# keyboard.net
KiCad netlist of a schematic drawn in EAGLE
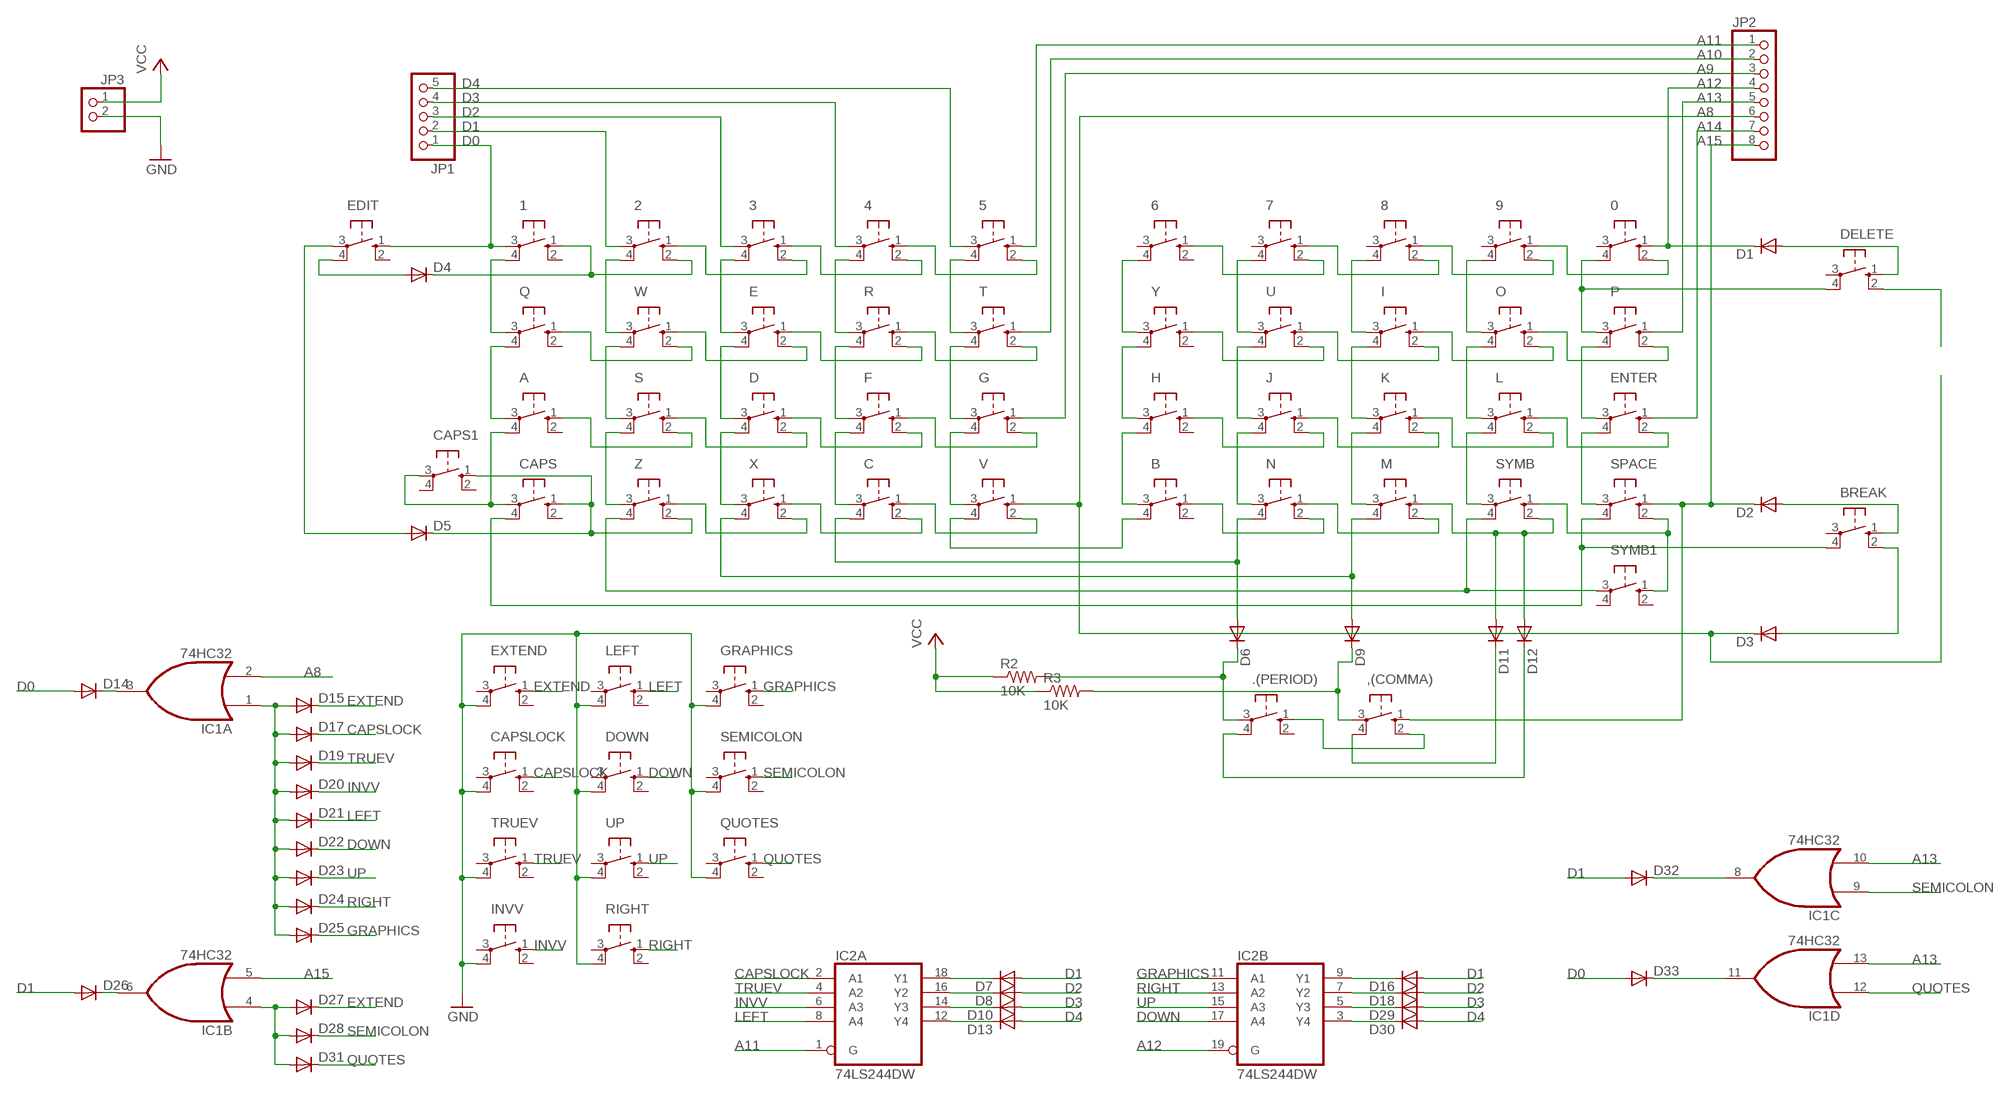
[diagram p0: schematic, sheet 1]

(export (version "E")
  (design (tool "Eeschema 10.0.6"))
  (components
    (comp (ref ",(COMMA)")
      (value "40-XX")
      (footprint "eagle-import:B3F-40XX")
      (fields (field (name "MF") "OMRON COMPONENTS USA") (field (name "MPN") "B3F-4000"))
      (libsource (lib "eagle-import") (part "40-XX"))
    )
    (comp (ref ".(PERIOD)")
      (value "40-XX")
      (footprint "eagle-import:B3F-40XX")
      (fields (field (name "MF") "OMRON COMPONENTS USA") (field (name "MPN") "B3F-4000"))
      (libsource (lib "eagle-import") (part "40-XX"))
    )
    (comp (ref "0")
      (value "40-XX")
      (footprint "eagle-import:B3F-40XX")
      (fields (field (name "MF") "OMRON COMPONENTS USA") (field (name "MPN") "B3F-4000"))
      (libsource (lib "eagle-import") (part "40-XX"))
    )
    (comp (ref "1")
      (value "40-XX")
      (footprint "eagle-import:B3F-40XX")
      (fields (field (name "MF") "OMRON COMPONENTS USA") (field (name "MPN") "B3F-4000"))
      (libsource (lib "eagle-import") (part "40-XX"))
    )
    (comp (ref "2")
      (value "40-XX")
      (footprint "eagle-import:B3F-40XX")
      (fields (field (name "MF") "OMRON COMPONENTS USA") (field (name "MPN") "B3F-4000"))
      (libsource (lib "eagle-import") (part "40-XX"))
    )
    (comp (ref "3")
      (value "40-XX")
      (footprint "eagle-import:B3F-40XX")
      (fields (field (name "MF") "OMRON COMPONENTS USA") (field (name "MPN") "B3F-4000"))
      (libsource (lib "eagle-import") (part "40-XX"))
    )
    (comp (ref "4")
      (value "40-XX")
      (footprint "eagle-import:B3F-40XX")
      (fields (field (name "MF") "OMRON COMPONENTS USA") (field (name "MPN") "B3F-4000"))
      (libsource (lib "eagle-import") (part "40-XX"))
    )
    (comp (ref "5")
      (value "40-XX")
      (footprint "eagle-import:B3F-40XX")
      (fields (field (name "MF") "OMRON COMPONENTS USA") (field (name "MPN") "B3F-4000"))
      (libsource (lib "eagle-import") (part "40-XX"))
    )
    (comp (ref "6")
      (value "40-XX")
      (footprint "eagle-import:B3F-40XX")
      (fields (field (name "MF") "OMRON COMPONENTS USA") (field (name "MPN") "B3F-4000"))
      (libsource (lib "eagle-import") (part "40-XX"))
    )
    (comp (ref "7")
      (value "40-XX")
      (footprint "eagle-import:B3F-40XX")
      (fields (field (name "MF") "OMRON COMPONENTS USA") (field (name "MPN") "B3F-4000"))
      (libsource (lib "eagle-import") (part "40-XX"))
    )
    (comp (ref "8")
      (value "40-XX")
      (footprint "eagle-import:B3F-40XX")
      (fields (field (name "MF") "OMRON COMPONENTS USA") (field (name "MPN") "B3F-4000"))
      (libsource (lib "eagle-import") (part "40-XX"))
    )
    (comp (ref "9")
      (value "40-XX")
      (footprint "eagle-import:B3F-40XX")
      (fields (field (name "MF") "OMRON COMPONENTS USA") (field (name "MPN") "B3F-4000"))
      (libsource (lib "eagle-import") (part "40-XX"))
    )
    (comp (ref "A")
      (value "40-XX")
      (footprint "eagle-import:B3F-40XX")
      (fields (field (name "MF") "OMRON COMPONENTS USA") (field (name "MPN") "B3F-4000"))
      (libsource (lib "eagle-import") (part "40-XX"))
    )
    (comp (ref "B")
      (value "40-XX")
      (footprint "eagle-import:B3F-40XX")
      (fields (field (name "MF") "OMRON COMPONENTS USA") (field (name "MPN") "B3F-4000"))
      (libsource (lib "eagle-import") (part "40-XX"))
    )
    (comp (ref "BREAK")
      (value "40-XX")
      (footprint "eagle-import:B3F-40XX")
      (fields (field (name "MF") "OMRON COMPONENTS USA") (field (name "MPN") "B3F-4000"))
      (libsource (lib "eagle-import") (part "40-XX"))
    )
    (comp (ref "C")
      (value "40-XX")
      (footprint "eagle-import:B3F-40XX")
      (fields (field (name "MF") "OMRON COMPONENTS USA") (field (name "MPN") "B3F-4000"))
      (libsource (lib "eagle-import") (part "40-XX"))
    )
    (comp (ref "CAPS")
      (value "40-XX")
      (footprint "eagle-import:B3F-40XX")
      (fields (field (name "MF") "OMRON COMPONENTS USA") (field (name "MPN") "B3F-4000"))
      (libsource (lib "eagle-import") (part "40-XX"))
    )
    (comp (ref "CAPS1")
      (value "40-XX")
      (footprint "eagle-import:B3F-40XX")
      (fields (field (name "MF") "OMRON COMPONENTS USA") (field (name "MPN") "B3F-4000"))
      (libsource (lib "eagle-import") (part "40-XX"))
    )
    (comp (ref "CAPSLOCK")
      (value "40-XX")
      (footprint "eagle-import:B3F-40XX")
      (fields (field (name "MF") "OMRON COMPONENTS USA") (field (name "MPN") "B3F-4000"))
      (libsource (lib "eagle-import") (part "40-XX"))
    )
    (comp (ref "D")
      (value "40-XX")
      (footprint "eagle-import:B3F-40XX")
      (fields (field (name "MF") "OMRON COMPONENTS USA") (field (name "MPN") "B3F-4000"))
      (libsource (lib "eagle-import") (part "40-XX"))
    )
    (comp (ref "D1")
      (value "DIODE-SMC")
      (footprint "eagle-import:SMC")
      (libsource (lib "eagle-import") (part "DIODE-SMC"))
    )
    (comp (ref "D2")
      (value "DIODE-SMC")
      (footprint "eagle-import:SMC")
      (libsource (lib "eagle-import") (part "DIODE-SMC"))
    )
    (comp (ref "D3")
      (value "DIODE-SMC")
      (footprint "eagle-import:SMC")
      (libsource (lib "eagle-import") (part "DIODE-SMC"))
    )
    (comp (ref "D4")
      (value "DIODE-SMC")
      (footprint "eagle-import:SMC")
      (libsource (lib "eagle-import") (part "DIODE-SMC"))
    )
    (comp (ref "D5")
      (value "DIODE-SMC")
      (footprint "eagle-import:SMC")
      (libsource (lib "eagle-import") (part "DIODE-SMC"))
    )
    (comp (ref "D6")
      (value "DIODE-SMC")
      (footprint "eagle-import:SMC")
      (libsource (lib "eagle-import") (part "DIODE-SMC"))
    )
    (comp (ref "D7")
      (value "DIODE-SMC")
      (footprint "eagle-import:SMC")
      (libsource (lib "eagle-import") (part "DIODE-SMC"))
    )
    (comp (ref "D8")
      (value "DIODE-SMC")
      (footprint "eagle-import:SMC")
      (libsource (lib "eagle-import") (part "DIODE-SMC"))
    )
    (comp (ref "D9")
      (value "DIODE-SMC")
      (footprint "eagle-import:SMC")
      (libsource (lib "eagle-import") (part "DIODE-SMC"))
    )
    (comp (ref "D10")
      (value "DIODE-SMC")
      (footprint "eagle-import:SMC")
      (libsource (lib "eagle-import") (part "DIODE-SMC"))
    )
    (comp (ref "D11")
      (value "DIODE-SMC")
      (footprint "eagle-import:SMC")
      (libsource (lib "eagle-import") (part "DIODE-SMC"))
    )
    (comp (ref "D12")
      (value "DIODE-SMC")
      (footprint "eagle-import:SMC")
      (libsource (lib "eagle-import") (part "DIODE-SMC"))
    )
    (comp (ref "D13")
      (value "DIODE-SMC")
      (footprint "eagle-import:SMC")
      (libsource (lib "eagle-import") (part "DIODE-SMC"))
    )
    (comp (ref "D14")
      (value "DIODE-SMC")
      (footprint "eagle-import:SMC")
      (libsource (lib "eagle-import") (part "DIODE-SMC"))
    )
    (comp (ref "D15")
      (value "DIODE-SMC")
      (footprint "eagle-import:SMC")
      (libsource (lib "eagle-import") (part "DIODE-SMC"))
    )
    (comp (ref "D16")
      (value "DIODE-SMC")
      (footprint "eagle-import:SMC")
      (libsource (lib "eagle-import") (part "DIODE-SMC"))
    )
    (comp (ref "D17")
      (value "DIODE-SMC")
      (footprint "eagle-import:SMC")
      (libsource (lib "eagle-import") (part "DIODE-SMC"))
    )
    (comp (ref "D18")
      (value "DIODE-SMC")
      (footprint "eagle-import:SMC")
      (libsource (lib "eagle-import") (part "DIODE-SMC"))
    )
    (comp (ref "D19")
      (value "DIODE-SMC")
      (footprint "eagle-import:SMC")
      (libsource (lib "eagle-import") (part "DIODE-SMC"))
    )
    (comp (ref "D20")
      (value "DIODE-SMC")
      (footprint "eagle-import:SMC")
      (libsource (lib "eagle-import") (part "DIODE-SMC"))
    )
    (comp (ref "D21")
      (value "DIODE-SMC")
      (footprint "eagle-import:SMC")
      (libsource (lib "eagle-import") (part "DIODE-SMC"))
    )
    (comp (ref "D22")
      (value "DIODE-SMC")
      (footprint "eagle-import:SMC")
      (libsource (lib "eagle-import") (part "DIODE-SMC"))
    )
    (comp (ref "D23")
      (value "DIODE-SMC")
      (footprint "eagle-import:SMC")
      (libsource (lib "eagle-import") (part "DIODE-SMC"))
    )
    (comp (ref "D24")
      (value "DIODE-SMC")
      (footprint "eagle-import:SMC")
      (libsource (lib "eagle-import") (part "DIODE-SMC"))
    )
    (comp (ref "D25")
      (value "DIODE-SMC")
      (footprint "eagle-import:SMC")
      (libsource (lib "eagle-import") (part "DIODE-SMC"))
    )
    (comp (ref "D26")
      (value "DIODE-SMC")
      (footprint "eagle-import:SMC")
      (libsource (lib "eagle-import") (part "DIODE-SMC"))
    )
    (comp (ref "D27")
      (value "DIODE-SMC")
      (footprint "eagle-import:SMC")
      (libsource (lib "eagle-import") (part "DIODE-SMC"))
    )
    (comp (ref "D28")
      (value "DIODE-SMC")
      (footprint "eagle-import:SMC")
      (libsource (lib "eagle-import") (part "DIODE-SMC"))
    )
    (comp (ref "D29")
      (value "DIODE-SMC")
      (footprint "eagle-import:SMC")
      (libsource (lib "eagle-import") (part "DIODE-SMC"))
    )
    (comp (ref "D30")
      (value "DIODE-SMC")
      (footprint "eagle-import:SMC")
      (libsource (lib "eagle-import") (part "DIODE-SMC"))
    )
    (comp (ref "D31")
      (value "DIODE-SMC")
      (footprint "eagle-import:SMC")
      (libsource (lib "eagle-import") (part "DIODE-SMC"))
    )
    (comp (ref "D32")
      (value "DIODE-SMC")
      (footprint "eagle-import:SMC")
      (libsource (lib "eagle-import") (part "DIODE-SMC"))
    )
    (comp (ref "D33")
      (value "DIODE-SMC")
      (footprint "eagle-import:SMC")
      (libsource (lib "eagle-import") (part "DIODE-SMC"))
    )
    (comp (ref "DELETE")
      (value "40-XX")
      (footprint "eagle-import:B3F-40XX")
      (fields (field (name "MF") "OMRON COMPONENTS USA") (field (name "MPN") "B3F-4000"))
      (libsource (lib "eagle-import") (part "40-XX"))
    )
    (comp (ref "DOWN")
      (value "40-XX")
      (footprint "eagle-import:B3F-40XX")
      (fields (field (name "MF") "OMRON COMPONENTS USA") (field (name "MPN") "B3F-4000"))
      (libsource (lib "eagle-import") (part "40-XX"))
    )
    (comp (ref "E")
      (value "40-XX")
      (footprint "eagle-import:B3F-40XX")
      (fields (field (name "MF") "OMRON COMPONENTS USA") (field (name "MPN") "B3F-4000"))
      (libsource (lib "eagle-import") (part "40-XX"))
    )
    (comp (ref "EDIT")
      (value "40-XX")
      (footprint "eagle-import:B3F-40XX")
      (fields (field (name "MF") "OMRON COMPONENTS USA") (field (name "MPN") "B3F-4000"))
      (libsource (lib "eagle-import") (part "40-XX"))
    )
    (comp (ref "ENTER")
      (value "40-XX")
      (footprint "eagle-import:B3F-40XX")
      (fields (field (name "MF") "OMRON COMPONENTS USA") (field (name "MPN") "B3F-4000"))
      (libsource (lib "eagle-import") (part "40-XX"))
    )
    (comp (ref "EXTEND")
      (value "40-XX")
      (footprint "eagle-import:B3F-40XX")
      (fields (field (name "MF") "OMRON COMPONENTS USA") (field (name "MPN") "B3F-4000"))
      (libsource (lib "eagle-import") (part "40-XX"))
    )
    (comp (ref "F")
      (value "40-XX")
      (footprint "eagle-import:B3F-40XX")
      (fields (field (name "MF") "OMRON COMPONENTS USA") (field (name "MPN") "B3F-4000"))
      (libsource (lib "eagle-import") (part "40-XX"))
    )
    (comp (ref "G")
      (value "40-XX")
      (footprint "eagle-import:B3F-40XX")
      (fields (field (name "MF") "OMRON COMPONENTS USA") (field (name "MPN") "B3F-4000"))
      (libsource (lib "eagle-import") (part "40-XX"))
    )
    (comp (ref "GRAPHICS")
      (value "40-XX")
      (footprint "eagle-import:B3F-40XX")
      (fields (field (name "MF") "OMRON COMPONENTS USA") (field (name "MPN") "B3F-4000"))
      (libsource (lib "eagle-import") (part "40-XX"))
    )
    (comp (ref "H")
      (value "40-XX")
      (footprint "eagle-import:B3F-40XX")
      (fields (field (name "MF") "OMRON COMPONENTS USA") (field (name "MPN") "B3F-4000"))
      (libsource (lib "eagle-import") (part "40-XX"))
    )
    (comp (ref "I")
      (value "40-XX")
      (footprint "eagle-import:B3F-40XX")
      (fields (field (name "MF") "OMRON COMPONENTS USA") (field (name "MPN") "B3F-4000"))
      (libsource (lib "eagle-import") (part "40-XX"))
    )
    (comp (ref "IC1")
      (value "74HC32")
      (footprint "eagle-import:SO14")
      (libsource (lib "eagle-import") (part "7432DS"))
    )
    (comp (ref "IC2")
      (value "74LS244DW")
      (footprint "eagle-import:SO20W")
      (libsource (lib "eagle-import") (part "74244DWLS"))
    )
    (comp (ref "INVV")
      (value "40-XX")
      (footprint "eagle-import:B3F-40XX")
      (fields (field (name "MF") "OMRON COMPONENTS USA") (field (name "MPN") "B3F-4000"))
      (libsource (lib "eagle-import") (part "40-XX"))
    )
    (comp (ref "J")
      (value "40-XX")
      (footprint "eagle-import:B3F-40XX")
      (fields (field (name "MF") "OMRON COMPONENTS USA") (field (name "MPN") "B3F-4000"))
      (libsource (lib "eagle-import") (part "40-XX"))
    )
    (comp (ref "JP1")
      (value "PINHD-1X5")
      (footprint "eagle-import:1X05")
      (libsource (lib "eagle-import") (part "PINHD-1X5"))
    )
    (comp (ref "JP2")
      (value "PINHD-1X8")
      (footprint "eagle-import:1X08")
      (libsource (lib "eagle-import") (part "PINHD-1X8"))
    )
    (comp (ref "JP3")
      (value "PINHD-1X2")
      (footprint "eagle-import:1X02")
      (libsource (lib "eagle-import") (part "PINHD-1X2"))
    )
    (comp (ref "K")
      (value "40-XX")
      (footprint "eagle-import:B3F-40XX")
      (fields (field (name "MF") "OMRON COMPONENTS USA") (field (name "MPN") "B3F-4000"))
      (libsource (lib "eagle-import") (part "40-XX"))
    )
    (comp (ref "L")
      (value "40-XX")
      (footprint "eagle-import:B3F-40XX")
      (fields (field (name "MF") "OMRON COMPONENTS USA") (field (name "MPN") "B3F-4000"))
      (libsource (lib "eagle-import") (part "40-XX"))
    )
    (comp (ref "LEFT")
      (value "40-XX")
      (footprint "eagle-import:B3F-40XX")
      (fields (field (name "MF") "OMRON COMPONENTS USA") (field (name "MPN") "B3F-4000"))
      (libsource (lib "eagle-import") (part "40-XX"))
    )
    (comp (ref "M")
      (value "40-XX")
      (footprint "eagle-import:B3F-40XX")
      (fields (field (name "MF") "OMRON COMPONENTS USA") (field (name "MPN") "B3F-4000"))
      (libsource (lib "eagle-import") (part "40-XX"))
    )
    (comp (ref "N")
      (value "40-XX")
      (footprint "eagle-import:B3F-40XX")
      (fields (field (name "MF") "OMRON COMPONENTS USA") (field (name "MPN") "B3F-4000"))
      (libsource (lib "eagle-import") (part "40-XX"))
    )
    (comp (ref "O")
      (value "40-XX")
      (footprint "eagle-import:B3F-40XX")
      (fields (field (name "MF") "OMRON COMPONENTS USA") (field (name "MPN") "B3F-4000"))
      (libsource (lib "eagle-import") (part "40-XX"))
    )
    (comp (ref "P")
      (value "40-XX")
      (footprint "eagle-import:B3F-40XX")
      (fields (field (name "MF") "OMRON COMPONENTS USA") (field (name "MPN") "B3F-4000"))
      (libsource (lib "eagle-import") (part "40-XX"))
    )
    (comp (ref "Q")
      (value "40-XX")
      (footprint "eagle-import:B3F-40XX")
      (fields (field (name "MF") "OMRON COMPONENTS USA") (field (name "MPN") "B3F-4000"))
      (libsource (lib "eagle-import") (part "40-XX"))
    )
    (comp (ref "QUOTES")
      (value "40-XX")
      (footprint "eagle-import:B3F-40XX")
      (fields (field (name "MF") "OMRON COMPONENTS USA") (field (name "MPN") "B3F-4000"))
      (libsource (lib "eagle-import") (part "40-XX"))
    )
    (comp (ref "R")
      (value "40-XX")
      (footprint "eagle-import:B3F-40XX")
      (fields (field (name "MF") "OMRON COMPONENTS USA") (field (name "MPN") "B3F-4000"))
      (libsource (lib "eagle-import") (part "40-XX"))
    )
    (comp (ref "R2")
      (value "10K")
      (footprint "eagle-import:M0805")
      (libsource (lib "eagle-import") (part "R-US_M0805"))
    )
    (comp (ref "R3")
      (value "10K")
      (footprint "eagle-import:M0805")
      (libsource (lib "eagle-import") (part "R-US_M0805"))
    )
    (comp (ref "RIGHT")
      (value "40-XX")
      (footprint "eagle-import:B3F-40XX")
      (fields (field (name "MF") "OMRON COMPONENTS USA") (field (name "MPN") "B3F-4000"))
      (libsource (lib "eagle-import") (part "40-XX"))
    )
    (comp (ref "S")
      (value "40-XX")
      (footprint "eagle-import:B3F-40XX")
      (fields (field (name "MF") "OMRON COMPONENTS USA") (field (name "MPN") "B3F-4000"))
      (libsource (lib "eagle-import") (part "40-XX"))
    )
    (comp (ref "SEMICOLON")
      (value "40-XX")
      (footprint "eagle-import:B3F-40XX")
      (fields (field (name "MF") "OMRON COMPONENTS USA") (field (name "MPN") "B3F-4000"))
      (libsource (lib "eagle-import") (part "40-XX"))
    )
    (comp (ref "SPACE")
      (value "40-XX")
      (footprint "eagle-import:B3F-40XX")
      (fields (field (name "MF") "OMRON COMPONENTS USA") (field (name "MPN") "B3F-4000"))
      (libsource (lib "eagle-import") (part "40-XX"))
    )
    (comp (ref "SYMB")
      (value "40-XX")
      (footprint "eagle-import:B3F-40XX")
      (fields (field (name "MF") "OMRON COMPONENTS USA") (field (name "MPN") "B3F-4000"))
      (libsource (lib "eagle-import") (part "40-XX"))
    )
    (comp (ref "SYMB1")
      (value "40-XX")
      (footprint "eagle-import:B3F-40XX")
      (fields (field (name "MF") "OMRON COMPONENTS USA") (field (name "MPN") "B3F-4000"))
      (libsource (lib "eagle-import") (part "40-XX"))
    )
    (comp (ref "T")
      (value "40-XX")
      (footprint "eagle-import:B3F-40XX")
      (fields (field (name "MF") "OMRON COMPONENTS USA") (field (name "MPN") "B3F-4000"))
      (libsource (lib "eagle-import") (part "40-XX"))
    )
    (comp (ref "TRUEV")
      (value "40-XX")
      (footprint "eagle-import:B3F-40XX")
      (fields (field (name "MF") "OMRON COMPONENTS USA") (field (name "MPN") "B3F-4000"))
      (libsource (lib "eagle-import") (part "40-XX"))
    )
    (comp (ref "U")
      (value "40-XX")
      (footprint "eagle-import:B3F-40XX")
      (fields (field (name "MF") "OMRON COMPONENTS USA") (field (name "MPN") "B3F-4000"))
      (libsource (lib "eagle-import") (part "40-XX"))
    )
    (comp (ref "UP")
      (value "40-XX")
      (footprint "eagle-import:B3F-40XX")
      (fields (field (name "MF") "OMRON COMPONENTS USA") (field (name "MPN") "B3F-4000"))
      (libsource (lib "eagle-import") (part "40-XX"))
    )
    (comp (ref "V")
      (value "40-XX")
      (footprint "eagle-import:B3F-40XX")
      (fields (field (name "MF") "OMRON COMPONENTS USA") (field (name "MPN") "B3F-4000"))
      (libsource (lib "eagle-import") (part "40-XX"))
    )
    (comp (ref "W")
      (value "40-XX")
      (footprint "eagle-import:B3F-40XX")
      (fields (field (name "MF") "OMRON COMPONENTS USA") (field (name "MPN") "B3F-4000"))
      (libsource (lib "eagle-import") (part "40-XX"))
    )
    (comp (ref "X")
      (value "40-XX")
      (footprint "eagle-import:B3F-40XX")
      (fields (field (name "MF") "OMRON COMPONENTS USA") (field (name "MPN") "B3F-4000"))
      (libsource (lib "eagle-import") (part "40-XX"))
    )
    (comp (ref "Y")
      (value "40-XX")
      (footprint "eagle-import:B3F-40XX")
      (fields (field (name "MF") "OMRON COMPONENTS USA") (field (name "MPN") "B3F-4000"))
      (libsource (lib "eagle-import") (part "40-XX"))
    )
    (comp (ref "Z")
      (value "40-XX")
      (footprint "eagle-import:B3F-40XX")
      (fields (field (name "MF") "OMRON COMPONENTS USA") (field (name "MPN") "B3F-4000"))
      (libsource (lib "eagle-import") (part "40-XX"))
    )
  )
  (nets
    (net (code "1") (name "/A8") (class "Default")
      (node (ref "D3") (pin "C") (pinfunction "C_C") (pintype "passive"))
      (node (ref "IC1") (pin "2") (pinfunction "I1_2") (pintype "input"))
      (node (ref "JP2") (pin "6") (pinfunction "6_6") (pintype "passive"))
      (node (ref "V") (pin "1") (pinfunction "S_1") (pintype "passive"))
    )
    (net (code "2") (name "/A9") (class "Default")
      (node (ref "G") (pin "1") (pinfunction "S_1") (pintype "passive"))
      (node (ref "JP2") (pin "3") (pinfunction "3_3") (pintype "passive"))
    )
    (net (code "3") (name "/A10") (class "Default")
      (node (ref "JP2") (pin "2") (pinfunction "2_2") (pintype "passive"))
      (node (ref "T") (pin "1") (pinfunction "S_1") (pintype "passive"))
    )
    (net (code "4") (name "/A11") (class "Default")
      (node (ref "5") (pin "1") (pinfunction "S_1") (pintype "passive"))
      (node (ref "IC2") (pin "1") (pinfunction "G_1") (pintype "input"))
      (node (ref "JP2") (pin "1") (pinfunction "1_1") (pintype "passive"))
    )
    (net (code "5") (name "/A12") (class "Default")
      (node (ref "0") (pin "1") (pinfunction "S_1") (pintype "passive"))
      (node (ref "D1") (pin "C") (pinfunction "C_C") (pintype "passive"))
      (node (ref "IC2") (pin "19") (pinfunction "G_19") (pintype "input"))
      (node (ref "JP2") (pin "4") (pinfunction "4_4") (pintype "passive"))
    )
    (net (code "6") (name "/A13") (class "Default")
      (node (ref "IC1") (pin "10") (pinfunction "I1_10") (pintype "input"))
      (node (ref "IC1") (pin "13") (pinfunction "I1_13") (pintype "input"))
      (node (ref "JP2") (pin "5") (pinfunction "5_5") (pintype "passive"))
      (node (ref "P") (pin "1") (pinfunction "S_1") (pintype "passive"))
    )
    (net (code "7") (name "/A14") (class "Default")
      (node (ref "ENTER") (pin "1") (pinfunction "S_1") (pintype "passive"))
      (node (ref "JP2") (pin "7") (pinfunction "7_7") (pintype "passive"))
    )
    (net (code "8") (name "/A15") (class "Default")
      (node (ref ",(COMMA)") (pin "1") (pinfunction "S_1") (pintype "passive"))
      (node (ref "D2") (pin "C") (pinfunction "C_C") (pintype "passive"))
      (node (ref "IC1") (pin "5") (pinfunction "I1_5") (pintype "input"))
      (node (ref "JP2") (pin "8") (pinfunction "8_8") (pintype "passive"))
      (node (ref "SPACE") (pin "1") (pinfunction "S_1") (pintype "passive"))
    )
    (net (code "9") (name "/CAPSLOCK") (class "Default")
      (node (ref "CAPSLOCK") (pin "1") (pinfunction "S_1") (pintype "passive"))
      (node (ref "D17") (pin "C") (pinfunction "C_C") (pintype "passive"))
      (node (ref "IC2") (pin "2") (pinfunction "A1_2") (pintype "input"))
    )
    (net (code "10") (name "/D0") (class "Default")
      (node (ref "1") (pin "3") (pinfunction "P_3") (pintype "passive"))
      (node (ref "D14") (pin "A") (pinfunction "A_A") (pintype "passive"))
      (node (ref "D33") (pin "A") (pinfunction "A_A") (pintype "passive"))
      (node (ref "EDIT") (pin "1") (pinfunction "S_1") (pintype "passive"))
      (node (ref "JP1") (pin "1") (pinfunction "1_1") (pintype "passive"))
    )
    (net (code "11") (name "/D1") (class "Default")
      (node (ref "2") (pin "3") (pinfunction "P_3") (pintype "passive"))
      (node (ref "D16") (pin "A") (pinfunction "A_A") (pintype "passive"))
      (node (ref "D26") (pin "A") (pinfunction "A_A") (pintype "passive"))
      (node (ref "D32") (pin "A") (pinfunction "A_A") (pintype "passive"))
      (node (ref "D7") (pin "A") (pinfunction "A_A") (pintype "passive"))
      (node (ref "JP1") (pin "2") (pinfunction "2_2") (pintype "passive"))
    )
    (net (code "12") (name "/D2") (class "Default")
      (node (ref "3") (pin "3") (pinfunction "P_3") (pintype "passive"))
      (node (ref "D18") (pin "A") (pinfunction "A_A") (pintype "passive"))
      (node (ref "D8") (pin "A") (pinfunction "A_A") (pintype "passive"))
      (node (ref "JP1") (pin "3") (pinfunction "3_3") (pintype "passive"))
    )
    (net (code "13") (name "/D3") (class "Default")
      (node (ref "4") (pin "3") (pinfunction "P_3") (pintype "passive"))
      (node (ref "D10") (pin "A") (pinfunction "A_A") (pintype "passive"))
      (node (ref "D29") (pin "A") (pinfunction "A_A") (pintype "passive"))
      (node (ref "JP1") (pin "4") (pinfunction "4_4") (pintype "passive"))
    )
    (net (code "14") (name "/D4") (class "Default")
      (node (ref "5") (pin "3") (pinfunction "P_3") (pintype "passive"))
      (node (ref "D13") (pin "A") (pinfunction "A_A") (pintype "passive"))
      (node (ref "D30") (pin "A") (pinfunction "A_A") (pintype "passive"))
      (node (ref "JP1") (pin "5") (pinfunction "5_5") (pintype "passive"))
    )
    (net (code "15") (name "/DOWN") (class "Default")
      (node (ref "D22") (pin "C") (pinfunction "C_C") (pintype "passive"))
      (node (ref "DOWN") (pin "1") (pinfunction "S_1") (pintype "passive"))
      (node (ref "IC2") (pin "17") (pinfunction "A4_17") (pintype "input"))
    )
    (net (code "16") (name "/EXTEND") (class "Default")
      (node (ref "D15") (pin "C") (pinfunction "C_C") (pintype "passive"))
      (node (ref "D27") (pin "C") (pinfunction "C_C") (pintype "passive"))
      (node (ref "EXTEND") (pin "1") (pinfunction "S_1") (pintype "passive"))
    )
    (net (code "17") (name "/GRAPHICS") (class "Default")
      (node (ref "D25") (pin "C") (pinfunction "C_C") (pintype "passive"))
      (node (ref "GRAPHICS") (pin "1") (pinfunction "S_1") (pintype "passive"))
      (node (ref "IC2") (pin "11") (pinfunction "A1_11") (pintype "input"))
    )
    (net (code "18") (name "/INVV") (class "Default")
      (node (ref "D20") (pin "C") (pinfunction "C_C") (pintype "passive"))
      (node (ref "IC2") (pin "6") (pinfunction "A3_6") (pintype "input"))
      (node (ref "INVV") (pin "1") (pinfunction "S_1") (pintype "passive"))
    )
    (net (code "19") (name "/LEFT") (class "Default")
      (node (ref "D21") (pin "C") (pinfunction "C_C") (pintype "passive"))
      (node (ref "IC2") (pin "8") (pinfunction "A4_8") (pintype "input"))
      (node (ref "LEFT") (pin "1") (pinfunction "S_1") (pintype "passive"))
    )
    (net (code "20") (name "/QUOTES") (class "Default")
      (node (ref "D31") (pin "C") (pinfunction "C_C") (pintype "passive"))
      (node (ref "IC1") (pin "12") (pinfunction "I0_12") (pintype "input"))
      (node (ref "QUOTES") (pin "1") (pinfunction "S_1") (pintype "passive"))
    )
    (net (code "21") (name "/RIGHT") (class "Default")
      (node (ref "D24") (pin "C") (pinfunction "C_C") (pintype "passive"))
      (node (ref "IC2") (pin "13") (pinfunction "A2_13") (pintype "input"))
      (node (ref "RIGHT") (pin "1") (pinfunction "S_1") (pintype "passive"))
    )
    (net (code "22") (name "/SEMICOLON") (class "Default")
      (node (ref "D28") (pin "C") (pinfunction "C_C") (pintype "passive"))
      (node (ref "IC1") (pin "9") (pinfunction "I0_9") (pintype "input"))
      (node (ref "SEMICOLON") (pin "1") (pinfunction "S_1") (pintype "passive"))
    )
    (net (code "23") (name "/TRUEV") (class "Default")
      (node (ref "D19") (pin "C") (pinfunction "C_C") (pintype "passive"))
      (node (ref "IC2") (pin "4") (pinfunction "A2_4") (pintype "input"))
      (node (ref "TRUEV") (pin "1") (pinfunction "S_1") (pintype "passive"))
    )
    (net (code "24") (name "/UP") (class "Default")
      (node (ref "D23") (pin "C") (pinfunction "C_C") (pintype "passive"))
      (node (ref "IC2") (pin "15") (pinfunction "A3_15") (pintype "input"))
      (node (ref "UP") (pin "1") (pinfunction "S_1") (pintype "passive"))
    )
    (net (code "25") (name "GND") (class "Default")
      (node (ref "CAPSLOCK") (pin "4") (pinfunction "P1_4") (pintype "passive"))
      (node (ref "DOWN") (pin "4") (pinfunction "P1_4") (pintype "passive"))
      (node (ref "EXTEND") (pin "4") (pinfunction "P1_4") (pintype "passive"))
      (node (ref "GRAPHICS") (pin "4") (pinfunction "P1_4") (pintype "passive"))
      (node (ref "INVV") (pin "4") (pinfunction "P1_4") (pintype "passive"))
      (node (ref "JP3") (pin "2") (pinfunction "2_2") (pintype "passive"))
      (node (ref "LEFT") (pin "4") (pinfunction "P1_4") (pintype "passive"))
      (node (ref "QUOTES") (pin "4") (pinfunction "P1_4") (pintype "passive"))
      (node (ref "RIGHT") (pin "4") (pinfunction "P1_4") (pintype "passive"))
      (node (ref "SEMICOLON") (pin "4") (pinfunction "P1_4") (pintype "passive"))
      (node (ref "TRUEV") (pin "4") (pinfunction "P1_4") (pintype "passive"))
      (node (ref "UP") (pin "4") (pinfunction "P1_4") (pintype "passive"))
    )
    (net (code "26") (name "Net-(,(COMMA)-P)") (class "Default")
      (node (ref ",(COMMA)") (pin "3") (pinfunction "P_3") (pintype "passive"))
      (node (ref "D9") (pin "C") (pinfunction "C_C") (pintype "passive"))
      (node (ref "R3") (pin "2") (pinfunction "2_2") (pintype "passive"))
    )
    (net (code "27") (name "Net-(,(COMMA)-P1)") (class "Default")
      (node (ref ",(COMMA)") (pin "4") (pinfunction "P1_4") (pintype "passive"))
      (node (ref "D11") (pin "C") (pinfunction "C_C") (pintype "passive"))
    )
    (net (code "28") (name "Net-(,(COMMA)-S1)") (class "Default")
      (node (ref ",(COMMA)") (pin "2") (pinfunction "S1_2") (pintype "passive"))
      (node (ref ".(PERIOD)") (pin "1") (pinfunction "S_1") (pintype "passive"))
    )
    (net (code "29") (name "Net-(.(PERIOD)-P)") (class "Default")
      (node (ref ".(PERIOD)") (pin "3") (pinfunction "P_3") (pintype "passive"))
      (node (ref "D6") (pin "C") (pinfunction "C_C") (pintype "passive"))
      (node (ref "R2") (pin "2") (pinfunction "2_2") (pintype "passive"))
    )
    (net (code "30") (name "Net-(.(PERIOD)-P1)") (class "Default")
      (node (ref ".(PERIOD)") (pin "4") (pinfunction "P1_4") (pintype "passive"))
      (node (ref "D12") (pin "C") (pinfunction "C_C") (pintype "passive"))
    )
    (net (code "31") (name "Net-(0-P1)") (class "Default")
      (node (ref "0") (pin "4") (pinfunction "P1_4") (pintype "passive"))
      (node (ref "DELETE") (pin "4") (pinfunction "P1_4") (pintype "passive"))
      (node (ref "P") (pin "3") (pinfunction "P_3") (pintype "passive"))
    )
    (net (code "32") (name "Net-(0-S1)") (class "Default")
      (node (ref "0") (pin "2") (pinfunction "S1_2") (pintype "passive"))
      (node (ref "9") (pin "1") (pinfunction "S_1") (pintype "passive"))
    )
    (net (code "33") (name "Net-(1-P1)") (class "Default")
      (node (ref "1") (pin "4") (pinfunction "P1_4") (pintype "passive"))
      (node (ref "Q") (pin "3") (pinfunction "P_3") (pintype "passive"))
    )
    (net (code "34") (name "Net-(1-S)") (class "Default")
      (node (ref "1") (pin "1") (pinfunction "S_1") (pintype "passive"))
      (node (ref "2") (pin "2") (pinfunction "S1_2") (pintype "passive"))
      (node (ref "D4") (pin "C") (pinfunction "C_C") (pintype "passive"))
    )
    (net (code "35") (name "Net-(2-P1)") (class "Default")
      (node (ref "2") (pin "4") (pinfunction "P1_4") (pintype "passive"))
      (node (ref "W") (pin "3") (pinfunction "P_3") (pintype "passive"))
    )
    (net (code "36") (name "Net-(2-S)") (class "Default")
      (node (ref "2") (pin "1") (pinfunction "S_1") (pintype "passive"))
      (node (ref "3") (pin "2") (pinfunction "S1_2") (pintype "passive"))
    )
    (net (code "37") (name "Net-(3-P1)") (class "Default")
      (node (ref "3") (pin "4") (pinfunction "P1_4") (pintype "passive"))
      (node (ref "E") (pin "3") (pinfunction "P_3") (pintype "passive"))
    )
    (net (code "38") (name "Net-(3-S)") (class "Default")
      (node (ref "3") (pin "1") (pinfunction "S_1") (pintype "passive"))
      (node (ref "4") (pin "2") (pinfunction "S1_2") (pintype "passive"))
    )
    (net (code "39") (name "Net-(4-P1)") (class "Default")
      (node (ref "4") (pin "4") (pinfunction "P1_4") (pintype "passive"))
      (node (ref "R") (pin "3") (pinfunction "P_3") (pintype "passive"))
    )
    (net (code "40") (name "Net-(4-S)") (class "Default")
      (node (ref "4") (pin "1") (pinfunction "S_1") (pintype "passive"))
      (node (ref "5") (pin "2") (pinfunction "S1_2") (pintype "passive"))
    )
    (net (code "41") (name "Net-(5-P1)") (class "Default")
      (node (ref "5") (pin "4") (pinfunction "P1_4") (pintype "passive"))
      (node (ref "T") (pin "3") (pinfunction "P_3") (pintype "passive"))
    )
    (net (code "42") (name "Net-(6-P1)") (class "Default")
      (node (ref "6") (pin "4") (pinfunction "P1_4") (pintype "passive"))
      (node (ref "Y") (pin "3") (pinfunction "P_3") (pintype "passive"))
    )
    (net (code "43") (name "Net-(6-S)") (class "Default")
      (node (ref "6") (pin "1") (pinfunction "S_1") (pintype "passive"))
      (node (ref "7") (pin "2") (pinfunction "S1_2") (pintype "passive"))
    )
    (net (code "44") (name "Net-(7-P1)") (class "Default")
      (node (ref "7") (pin "4") (pinfunction "P1_4") (pintype "passive"))
      (node (ref "U") (pin "3") (pinfunction "P_3") (pintype "passive"))
    )
    (net (code "45") (name "Net-(7-S)") (class "Default")
      (node (ref "7") (pin "1") (pinfunction "S_1") (pintype "passive"))
      (node (ref "8") (pin "2") (pinfunction "S1_2") (pintype "passive"))
    )
    (net (code "46") (name "Net-(8-P1)") (class "Default")
      (node (ref "8") (pin "4") (pinfunction "P1_4") (pintype "passive"))
      (node (ref "I") (pin "3") (pinfunction "P_3") (pintype "passive"))
    )
    (net (code "47") (name "Net-(8-S)") (class "Default")
      (node (ref "8") (pin "1") (pinfunction "S_1") (pintype "passive"))
      (node (ref "9") (pin "2") (pinfunction "S1_2") (pintype "passive"))
    )
    (net (code "48") (name "Net-(9-P1)") (class "Default")
      (node (ref "9") (pin "4") (pinfunction "P1_4") (pintype "passive"))
      (node (ref "O") (pin "3") (pinfunction "P_3") (pintype "passive"))
    )
    (net (code "49") (name "Net-(A-P)") (class "Default")
      (node (ref "A") (pin "3") (pinfunction "P_3") (pintype "passive"))
      (node (ref "Q") (pin "4") (pinfunction "P1_4") (pintype "passive"))
    )
    (net (code "50") (name "Net-(A-P1)") (class "Default")
      (node (ref "A") (pin "4") (pinfunction "P1_4") (pintype "passive"))
      (node (ref "CAPS") (pin "3") (pinfunction "P_3") (pintype "passive"))
      (node (ref "CAPS1") (pin "3") (pinfunction "P_3") (pintype "passive"))
    )
    (net (code "51") (name "Net-(A-S)") (class "Default")
      (node (ref "A") (pin "1") (pinfunction "S_1") (pintype "passive"))
      (node (ref "S") (pin "2") (pinfunction "S1_2") (pintype "passive"))
    )
    (net (code "52") (name "Net-(B-P)") (class "Default")
      (node (ref "B") (pin "3") (pinfunction "P_3") (pintype "passive"))
      (node (ref "H") (pin "4") (pinfunction "P1_4") (pintype "passive"))
    )
    (net (code "53") (name "Net-(B-P1)") (class "Default")
      (node (ref "B") (pin "4") (pinfunction "P1_4") (pintype "passive"))
      (node (ref "V") (pin "4") (pinfunction "P1_4") (pintype "passive"))
    )
    (net (code "54") (name "Net-(B-S)") (class "Default")
      (node (ref "B") (pin "1") (pinfunction "S_1") (pintype "passive"))
      (node (ref "N") (pin "2") (pinfunction "S1_2") (pintype "passive"))
    )
    (net (code "55") (name "Net-(BREAK-P1)") (class "Default")
      (node (ref "BREAK") (pin "4") (pinfunction "P1_4") (pintype "passive"))
      (node (ref "CAPS") (pin "4") (pinfunction "P1_4") (pintype "passive"))
      (node (ref "SPACE") (pin "4") (pinfunction "P1_4") (pintype "passive"))
    )
    (net (code "56") (name "Net-(BREAK-S)") (class "Default")
      (node (ref "BREAK") (pin "1") (pinfunction "S_1") (pintype "passive"))
      (node (ref "D2") (pin "A") (pinfunction "A_A") (pintype "passive"))
    )
    (net (code "57") (name "Net-(BREAK-S1)") (class "Default")
      (node (ref "BREAK") (pin "2") (pinfunction "S1_2") (pintype "passive"))
      (node (ref "D3") (pin "A") (pinfunction "A_A") (pintype "passive"))
    )
    (net (code "58") (name "Net-(C-P)") (class "Default")
      (node (ref "C") (pin "3") (pinfunction "P_3") (pintype "passive"))
      (node (ref "F") (pin "4") (pinfunction "P1_4") (pintype "passive"))
    )
    (net (code "59") (name "Net-(C-P1)") (class "Default")
      (node (ref "C") (pin "4") (pinfunction "P1_4") (pintype "passive"))
      (node (ref "D6") (pin "A") (pinfunction "A_A") (pintype "passive"))
      (node (ref "N") (pin "4") (pinfunction "P1_4") (pintype "passive"))
    )
    (net (code "60") (name "Net-(C-S)") (class "Default")
      (node (ref "C") (pin "1") (pinfunction "S_1") (pintype "passive"))
      (node (ref "V") (pin "2") (pinfunction "S1_2") (pintype "passive"))
    )
    (net (code "61") (name "Net-(C-S1)") (class "Default")
      (node (ref "C") (pin "2") (pinfunction "S1_2") (pintype "passive"))
      (node (ref "X") (pin "1") (pinfunction "S_1") (pintype "passive"))
    )
    (net (code "62") (name "Net-(CAPS-S)") (class "Default")
      (node (ref "CAPS") (pin "1") (pinfunction "S_1") (pintype "passive"))
      (node (ref "CAPS1") (pin "1") (pinfunction "S_1") (pintype "passive"))
      (node (ref "D5") (pin "C") (pinfunction "C_C") (pintype "passive"))
      (node (ref "Z") (pin "2") (pinfunction "S1_2") (pintype "passive"))
    )
    (net (code "63") (name "Net-(D-P)") (class "Default")
      (node (ref "D") (pin "3") (pinfunction "P_3") (pintype "passive"))
      (node (ref "E") (pin "4") (pinfunction "P1_4") (pintype "passive"))
    )
    (net (code "64") (name "Net-(D-P1)") (class "Default")
      (node (ref "D") (pin "4") (pinfunction "P1_4") (pintype "passive"))
      (node (ref "X") (pin "3") (pinfunction "P_3") (pintype "passive"))
    )
    (net (code "65") (name "Net-(D-S)") (class "Default")
      (node (ref "D") (pin "1") (pinfunction "S_1") (pintype "passive"))
      (node (ref "F") (pin "2") (pinfunction "S1_2") (pintype "passive"))
    )
    (net (code "66") (name "Net-(D-S1)") (class "Default")
      (node (ref "D") (pin "2") (pinfunction "S1_2") (pintype "passive"))
      (node (ref "S") (pin "1") (pinfunction "S_1") (pintype "passive"))
    )
    (net (code "67") (name "Net-(DELETE-S)") (class "Default")
      (node (ref "D1") (pin "A") (pinfunction "A_A") (pintype "passive"))
      (node (ref "DELETE") (pin "1") (pinfunction "S_1") (pintype "passive"))
    )
    (net (code "68") (name "Net-(E-S)") (class "Default")
      (node (ref "E") (pin "1") (pinfunction "S_1") (pintype "passive"))
      (node (ref "R") (pin "2") (pinfunction "S1_2") (pintype "passive"))
    )
    (net (code "69") (name "Net-(E-S1)") (class "Default")
      (node (ref "E") (pin "2") (pinfunction "S1_2") (pintype "passive"))
      (node (ref "W") (pin "1") (pinfunction "S_1") (pintype "passive"))
    )
    (net (code "70") (name "Net-(EDIT-P)") (class "Default")
      (node (ref "D5") (pin "A") (pinfunction "A_A") (pintype "passive"))
      (node (ref "EDIT") (pin "3") (pinfunction "P_3") (pintype "passive"))
    )
    (net (code "71") (name "Net-(EDIT-P1)") (class "Default")
      (node (ref "D4") (pin "A") (pinfunction "A_A") (pintype "passive"))
      (node (ref "EDIT") (pin "4") (pinfunction "P1_4") (pintype "passive"))
    )
    (net (code "72") (name "Net-(ENTER-P)") (class "Default")
      (node (ref "ENTER") (pin "3") (pinfunction "P_3") (pintype "passive"))
      (node (ref "P") (pin "4") (pinfunction "P1_4") (pintype "passive"))
    )
    (net (code "73") (name "Net-(ENTER-P1)") (class "Default")
      (node (ref "ENTER") (pin "4") (pinfunction "P1_4") (pintype "passive"))
      (node (ref "SPACE") (pin "3") (pinfunction "P_3") (pintype "passive"))
    )
    (net (code "74") (name "Net-(ENTER-S1)") (class "Default")
      (node (ref "ENTER") (pin "2") (pinfunction "S1_2") (pintype "passive"))
      (node (ref "L") (pin "1") (pinfunction "S_1") (pintype "passive"))
    )
    (net (code "75") (name "Net-(F-P)") (class "Default")
      (node (ref "F") (pin "3") (pinfunction "P_3") (pintype "passive"))
      (node (ref "R") (pin "4") (pinfunction "P1_4") (pintype "passive"))
    )
    (net (code "76") (name "Net-(F-S)") (class "Default")
      (node (ref "F") (pin "1") (pinfunction "S_1") (pintype "passive"))
      (node (ref "G") (pin "2") (pinfunction "S1_2") (pintype "passive"))
    )
    (net (code "77") (name "Net-(G-P)") (class "Default")
      (node (ref "G") (pin "3") (pinfunction "P_3") (pintype "passive"))
      (node (ref "T") (pin "4") (pinfunction "P1_4") (pintype "passive"))
    )
    (net (code "78") (name "Net-(G-P1)") (class "Default")
      (node (ref "G") (pin "4") (pinfunction "P1_4") (pintype "passive"))
      (node (ref "V") (pin "3") (pinfunction "P_3") (pintype "passive"))
    )
    (net (code "79") (name "Net-(H-P)") (class "Default")
      (node (ref "H") (pin "3") (pinfunction "P_3") (pintype "passive"))
      (node (ref "Y") (pin "4") (pinfunction "P1_4") (pintype "passive"))
    )
    (net (code "80") (name "Net-(H-S)") (class "Default")
      (node (ref "H") (pin "1") (pinfunction "S_1") (pintype "passive"))
      (node (ref "J") (pin "2") (pinfunction "S1_2") (pintype "passive"))
    )
    (net (code "81") (name "Net-(I-P1)") (class "Default")
      (node (ref "I") (pin "4") (pinfunction "P1_4") (pintype "passive"))
      (node (ref "K") (pin "3") (pinfunction "P_3") (pintype "passive"))
    )
    (net (code "82") (name "Net-(I-S)") (class "Default")
      (node (ref "I") (pin "1") (pinfunction "S_1") (pintype "passive"))
      (node (ref "O") (pin "2") (pinfunction "S1_2") (pintype "passive"))
    )
    (net (code "83") (name "Net-(I-S1)") (class "Default")
      (node (ref "I") (pin "2") (pinfunction "S1_2") (pintype "passive"))
      (node (ref "U") (pin "1") (pinfunction "S_1") (pintype "passive"))
    )
    (net (code "84") (name "Net-(IC1A-I0)") (class "Default")
      (node (ref "D15") (pin "A") (pinfunction "A_A") (pintype "passive"))
      (node (ref "D17") (pin "A") (pinfunction "A_A") (pintype "passive"))
      (node (ref "D19") (pin "A") (pinfunction "A_A") (pintype "passive"))
      (node (ref "D20") (pin "A") (pinfunction "A_A") (pintype "passive"))
      (node (ref "D21") (pin "A") (pinfunction "A_A") (pintype "passive"))
      (node (ref "D22") (pin "A") (pinfunction "A_A") (pintype "passive"))
      (node (ref "D23") (pin "A") (pinfunction "A_A") (pintype "passive"))
      (node (ref "D24") (pin "A") (pinfunction "A_A") (pintype "passive"))
      (node (ref "D25") (pin "A") (pinfunction "A_A") (pintype "passive"))
      (node (ref "IC1") (pin "1") (pinfunction "I0_1") (pintype "input"))
    )
    (net (code "85") (name "Net-(IC1A-O)") (class "Default")
      (node (ref "D14") (pin "C") (pinfunction "C_C") (pintype "passive"))
      (node (ref "IC1") (pin "3") (pinfunction "O_3") (pintype "output"))
    )
    (net (code "86") (name "Net-(IC1B-I0)") (class "Default")
      (node (ref "D27") (pin "A") (pinfunction "A_A") (pintype "passive"))
      (node (ref "D28") (pin "A") (pinfunction "A_A") (pintype "passive"))
      (node (ref "D31") (pin "A") (pinfunction "A_A") (pintype "passive"))
      (node (ref "IC1") (pin "4") (pinfunction "I0_4") (pintype "input"))
    )
    (net (code "87") (name "Net-(IC1B-O)") (class "Default")
      (node (ref "D26") (pin "C") (pinfunction "C_C") (pintype "passive"))
      (node (ref "IC1") (pin "6") (pinfunction "O_6") (pintype "output"))
    )
    (net (code "88") (name "Net-(IC1C-O)") (class "Default")
      (node (ref "D32") (pin "C") (pinfunction "C_C") (pintype "passive"))
      (node (ref "IC1") (pin "8") (pinfunction "O_8") (pintype "output"))
    )
    (net (code "89") (name "Net-(IC1D-O)") (class "Default")
      (node (ref "D33") (pin "C") (pinfunction "C_C") (pintype "passive"))
      (node (ref "IC1") (pin "11") (pinfunction "O_11") (pintype "output"))
    )
    (net (code "90") (name "Net-(IC2A-Y1)") (class "Default")
      (node (ref "D7") (pin "C") (pinfunction "C_C") (pintype "passive"))
      (node (ref "IC2") (pin "18") (pinfunction "Y1_18") (pintype "tri_state"))
    )
    (net (code "91") (name "Net-(IC2A-Y2)") (class "Default")
      (node (ref "D8") (pin "C") (pinfunction "C_C") (pintype "passive"))
      (node (ref "IC2") (pin "16") (pinfunction "Y2_16") (pintype "tri_state"))
    )
    (net (code "92") (name "Net-(IC2A-Y3)") (class "Default")
      (node (ref "D10") (pin "C") (pinfunction "C_C") (pintype "passive"))
      (node (ref "IC2") (pin "14") (pinfunction "Y3_14") (pintype "tri_state"))
    )
    (net (code "93") (name "Net-(IC2A-Y4)") (class "Default")
      (node (ref "D13") (pin "C") (pinfunction "C_C") (pintype "passive"))
      (node (ref "IC2") (pin "12") (pinfunction "Y4_12") (pintype "tri_state"))
    )
    (net (code "94") (name "Net-(IC2B-Y1)") (class "Default")
      (node (ref "D16") (pin "C") (pinfunction "C_C") (pintype "passive"))
      (node (ref "IC2") (pin "9") (pinfunction "Y1_9") (pintype "tri_state"))
    )
    (net (code "95") (name "Net-(IC2B-Y2)") (class "Default")
      (node (ref "D18") (pin "C") (pinfunction "C_C") (pintype "passive"))
      (node (ref "IC2") (pin "7") (pinfunction "Y2_7") (pintype "tri_state"))
    )
    (net (code "96") (name "Net-(IC2B-Y3)") (class "Default")
      (node (ref "D29") (pin "C") (pinfunction "C_C") (pintype "passive"))
      (node (ref "IC2") (pin "5") (pinfunction "Y3_5") (pintype "tri_state"))
    )
    (net (code "97") (name "Net-(IC2B-Y4)") (class "Default")
      (node (ref "D30") (pin "C") (pinfunction "C_C") (pintype "passive"))
      (node (ref "IC2") (pin "3") (pinfunction "Y4_3") (pintype "tri_state"))
    )
    (net (code "98") (name "Net-(J-P)") (class "Default")
      (node (ref "J") (pin "3") (pinfunction "P_3") (pintype "passive"))
      (node (ref "U") (pin "4") (pinfunction "P1_4") (pintype "passive"))
    )
    (net (code "99") (name "Net-(J-P1)") (class "Default")
      (node (ref "J") (pin "4") (pinfunction "P1_4") (pintype "passive"))
      (node (ref "N") (pin "3") (pinfunction "P_3") (pintype "passive"))
    )
    (net (code "100") (name "Net-(J-S)") (class "Default")
      (node (ref "J") (pin "1") (pinfunction "S_1") (pintype "passive"))
      (node (ref "K") (pin "2") (pinfunction "S1_2") (pintype "passive"))
    )
    (net (code "101") (name "Net-(K-P1)") (class "Default")
      (node (ref "K") (pin "4") (pinfunction "P1_4") (pintype "passive"))
      (node (ref "M") (pin "3") (pinfunction "P_3") (pintype "passive"))
    )
    (net (code "102") (name "Net-(K-S)") (class "Default")
      (node (ref "K") (pin "1") (pinfunction "S_1") (pintype "passive"))
      (node (ref "L") (pin "2") (pinfunction "S1_2") (pintype "passive"))
    )
    (net (code "103") (name "Net-(L-P)") (class "Default")
      (node (ref "L") (pin "3") (pinfunction "P_3") (pintype "passive"))
      (node (ref "O") (pin "4") (pinfunction "P1_4") (pintype "passive"))
    )
    (net (code "104") (name "Net-(L-P1)") (class "Default")
      (node (ref "L") (pin "4") (pinfunction "P1_4") (pintype "passive"))
      (node (ref "SYMB") (pin "3") (pinfunction "P_3") (pintype "passive"))
    )
    (net (code "105") (name "Net-(M-P1)") (class "Default")
      (node (ref "D9") (pin "A") (pinfunction "A_A") (pintype "passive"))
      (node (ref "M") (pin "4") (pinfunction "P1_4") (pintype "passive"))
      (node (ref "X") (pin "4") (pinfunction "P1_4") (pintype "passive"))
    )
    (net (code "106") (name "Net-(M-S)") (class "Default")
      (node (ref "D11") (pin "A") (pinfunction "A_A") (pintype "passive"))
      (node (ref "D12") (pin "A") (pinfunction "A_A") (pintype "passive"))
      (node (ref "M") (pin "1") (pinfunction "S_1") (pintype "passive"))
      (node (ref "SYMB") (pin "2") (pinfunction "S1_2") (pintype "passive"))
    )
    (net (code "107") (name "Net-(M-S1)") (class "Default")
      (node (ref "M") (pin "2") (pinfunction "S1_2") (pintype "passive"))
      (node (ref "N") (pin "1") (pinfunction "S_1") (pintype "passive"))
    )
    (net (code "108") (name "Net-(O-S)") (class "Default")
      (node (ref "O") (pin "1") (pinfunction "S_1") (pintype "passive"))
      (node (ref "P") (pin "2") (pinfunction "S1_2") (pintype "passive"))
    )
    (net (code "109") (name "Net-(Q-S)") (class "Default")
      (node (ref "Q") (pin "1") (pinfunction "S_1") (pintype "passive"))
      (node (ref "W") (pin "2") (pinfunction "S1_2") (pintype "passive"))
    )
    (net (code "110") (name "Net-(R-S)") (class "Default")
      (node (ref "R") (pin "1") (pinfunction "S_1") (pintype "passive"))
      (node (ref "T") (pin "2") (pinfunction "S1_2") (pintype "passive"))
    )
    (net (code "111") (name "Net-(S-P)") (class "Default")
      (node (ref "S") (pin "3") (pinfunction "P_3") (pintype "passive"))
      (node (ref "W") (pin "4") (pinfunction "P1_4") (pintype "passive"))
    )
    (net (code "112") (name "Net-(S-P1)") (class "Default")
      (node (ref "S") (pin "4") (pinfunction "P1_4") (pintype "passive"))
      (node (ref "Z") (pin "3") (pinfunction "P_3") (pintype "passive"))
    )
    (net (code "113") (name "Net-(SPACE-S1)") (class "Default")
      (node (ref "SPACE") (pin "2") (pinfunction "S1_2") (pintype "passive"))
      (node (ref "SYMB") (pin "1") (pinfunction "S_1") (pintype "passive"))
      (node (ref "SYMB1") (pin "1") (pinfunction "S_1") (pintype "passive"))
    )
    (net (code "114") (name "Net-(SYMB-P1)") (class "Default")
      (node (ref "SYMB") (pin "4") (pinfunction "P1_4") (pintype "passive"))
      (node (ref "SYMB1") (pin "3") (pinfunction "P_3") (pintype "passive"))
      (node (ref "Z") (pin "4") (pinfunction "P1_4") (pintype "passive"))
    )
    (net (code "115") (name "Net-(U-S1)") (class "Default")
      (node (ref "U") (pin "2") (pinfunction "S1_2") (pintype "passive"))
      (node (ref "Y") (pin "1") (pinfunction "S_1") (pintype "passive"))
    )
    (net (code "116") (name "Net-(X-S1)") (class "Default")
      (node (ref "X") (pin "2") (pinfunction "S1_2") (pintype "passive"))
      (node (ref "Z") (pin "1") (pinfunction "S_1") (pintype "passive"))
    )
    (net (code "117") (name "VCC") (class "Default")
      (node (ref "JP3") (pin "1") (pinfunction "1_1") (pintype "passive"))
      (node (ref "R2") (pin "1") (pinfunction "1_1") (pintype "passive"))
      (node (ref "R3") (pin "1") (pinfunction "1_1") (pintype "passive"))
    )
    (net (code "118") (name "unconnected-(.(PERIOD)-S1-Pad2)") (class "Default")
      (node (ref ".(PERIOD)") (pin "2") (pinfunction "S1_2") (pintype "passive"))
    )
    (net (code "119") (name "unconnected-(0-P-Pad3)") (class "Default")
      (node (ref "0") (pin "3") (pinfunction "P_3") (pintype "passive"))
    )
    (net (code "120") (name "unconnected-(1-S1-Pad2)") (class "Default")
      (node (ref "1") (pin "2") (pinfunction "S1_2") (pintype "passive"))
    )
    (net (code "121") (name "unconnected-(6-P-Pad3)") (class "Default")
      (node (ref "6") (pin "3") (pinfunction "P_3") (pintype "passive"))
    )
    (net (code "122") (name "unconnected-(6-S1-Pad2)") (class "Default")
      (node (ref "6") (pin "2") (pinfunction "S1_2") (pintype "passive"))
    )
    (net (code "123") (name "unconnected-(7-P-Pad3)") (class "Default")
      (node (ref "7") (pin "3") (pinfunction "P_3") (pintype "passive"))
    )
    (net (code "124") (name "unconnected-(8-P-Pad3)") (class "Default")
      (node (ref "8") (pin "3") (pinfunction "P_3") (pintype "passive"))
    )
    (net (code "125") (name "unconnected-(9-P-Pad3)") (class "Default")
      (node (ref "9") (pin "3") (pinfunction "P_3") (pintype "passive"))
    )
    (net (code "126") (name "unconnected-(A-S1-Pad2)") (class "Default")
      (node (ref "A") (pin "2") (pinfunction "S1_2") (pintype "passive"))
    )
    (net (code "127") (name "unconnected-(B-S1-Pad2)") (class "Default")
      (node (ref "B") (pin "2") (pinfunction "S1_2") (pintype "passive"))
    )
    (net (code "128") (name "unconnected-(BREAK-P-Pad3)") (class "Default")
      (node (ref "BREAK") (pin "3") (pinfunction "P_3") (pintype "passive"))
    )
    (net (code "129") (name "unconnected-(CAPS-S1-Pad2)") (class "Default")
      (node (ref "CAPS") (pin "2") (pinfunction "S1_2") (pintype "passive"))
    )
    (net (code "130") (name "unconnected-(CAPS1-P1-Pad4)") (class "Default")
      (node (ref "CAPS1") (pin "4") (pinfunction "P1_4") (pintype "passive"))
    )
    (net (code "131") (name "unconnected-(CAPS1-S1-Pad2)") (class "Default")
      (node (ref "CAPS1") (pin "2") (pinfunction "S1_2") (pintype "passive"))
    )
    (net (code "132") (name "unconnected-(CAPSLOCK-P-Pad3)") (class "Default")
      (node (ref "CAPSLOCK") (pin "3") (pinfunction "P_3") (pintype "passive"))
    )
    (net (code "133") (name "unconnected-(CAPSLOCK-S1-Pad2)") (class "Default")
      (node (ref "CAPSLOCK") (pin "2") (pinfunction "S1_2") (pintype "passive"))
    )
    (net (code "134") (name "unconnected-(DELETE-P-Pad3)") (class "Default")
      (node (ref "DELETE") (pin "3") (pinfunction "P_3") (pintype "passive"))
    )
    (net (code "135") (name "unconnected-(DELETE-S1-Pad2)") (class "Default")
      (node (ref "DELETE") (pin "2") (pinfunction "S1_2") (pintype "passive"))
    )
    (net (code "136") (name "unconnected-(DOWN-P-Pad3)") (class "Default")
      (node (ref "DOWN") (pin "3") (pinfunction "P_3") (pintype "passive"))
    )
    (net (code "137") (name "unconnected-(DOWN-S1-Pad2)") (class "Default")
      (node (ref "DOWN") (pin "2") (pinfunction "S1_2") (pintype "passive"))
    )
    (net (code "138") (name "unconnected-(EDIT-S1-Pad2)") (class "Default")
      (node (ref "EDIT") (pin "2") (pinfunction "S1_2") (pintype "passive"))
    )
    (net (code "139") (name "unconnected-(EXTEND-P-Pad3)") (class "Default")
      (node (ref "EXTEND") (pin "3") (pinfunction "P_3") (pintype "passive"))
    )
    (net (code "140") (name "unconnected-(EXTEND-S1-Pad2)") (class "Default")
      (node (ref "EXTEND") (pin "2") (pinfunction "S1_2") (pintype "passive"))
    )
    (net (code "141") (name "unconnected-(GRAPHICS-P-Pad3)") (class "Default")
      (node (ref "GRAPHICS") (pin "3") (pinfunction "P_3") (pintype "passive"))
    )
    (net (code "142") (name "unconnected-(GRAPHICS-S1-Pad2)") (class "Default")
      (node (ref "GRAPHICS") (pin "2") (pinfunction "S1_2") (pintype "passive"))
    )
    (net (code "143") (name "unconnected-(H-S1-Pad2)") (class "Default")
      (node (ref "H") (pin "2") (pinfunction "S1_2") (pintype "passive"))
    )
    (net (code "144") (name "unconnected-(INVV-P-Pad3)") (class "Default")
      (node (ref "INVV") (pin "3") (pinfunction "P_3") (pintype "passive"))
    )
    (net (code "145") (name "unconnected-(INVV-S1-Pad2)") (class "Default")
      (node (ref "INVV") (pin "2") (pinfunction "S1_2") (pintype "passive"))
    )
    (net (code "146") (name "unconnected-(LEFT-P-Pad3)") (class "Default")
      (node (ref "LEFT") (pin "3") (pinfunction "P_3") (pintype "passive"))
    )
    (net (code "147") (name "unconnected-(LEFT-S1-Pad2)") (class "Default")
      (node (ref "LEFT") (pin "2") (pinfunction "S1_2") (pintype "passive"))
    )
    (net (code "148") (name "unconnected-(Q-S1-Pad2)") (class "Default")
      (node (ref "Q") (pin "2") (pinfunction "S1_2") (pintype "passive"))
    )
    (net (code "149") (name "unconnected-(QUOTES-P-Pad3)") (class "Default")
      (node (ref "QUOTES") (pin "3") (pinfunction "P_3") (pintype "passive"))
    )
    (net (code "150") (name "unconnected-(QUOTES-S1-Pad2)") (class "Default")
      (node (ref "QUOTES") (pin "2") (pinfunction "S1_2") (pintype "passive"))
    )
    (net (code "151") (name "unconnected-(RIGHT-P-Pad3)") (class "Default")
      (node (ref "RIGHT") (pin "3") (pinfunction "P_3") (pintype "passive"))
    )
    (net (code "152") (name "unconnected-(RIGHT-S1-Pad2)") (class "Default")
      (node (ref "RIGHT") (pin "2") (pinfunction "S1_2") (pintype "passive"))
    )
    (net (code "153") (name "unconnected-(SEMICOLON-P-Pad3)") (class "Default")
      (node (ref "SEMICOLON") (pin "3") (pinfunction "P_3") (pintype "passive"))
    )
    (net (code "154") (name "unconnected-(SEMICOLON-S1-Pad2)") (class "Default")
      (node (ref "SEMICOLON") (pin "2") (pinfunction "S1_2") (pintype "passive"))
    )
    (net (code "155") (name "unconnected-(SYMB1-P1-Pad4)") (class "Default")
      (node (ref "SYMB1") (pin "4") (pinfunction "P1_4") (pintype "passive"))
    )
    (net (code "156") (name "unconnected-(SYMB1-S1-Pad2)") (class "Default")
      (node (ref "SYMB1") (pin "2") (pinfunction "S1_2") (pintype "passive"))
    )
    (net (code "157") (name "unconnected-(TRUEV-P-Pad3)") (class "Default")
      (node (ref "TRUEV") (pin "3") (pinfunction "P_3") (pintype "passive"))
    )
    (net (code "158") (name "unconnected-(TRUEV-S1-Pad2)") (class "Default")
      (node (ref "TRUEV") (pin "2") (pinfunction "S1_2") (pintype "passive"))
    )
    (net (code "159") (name "unconnected-(UP-P-Pad3)") (class "Default")
      (node (ref "UP") (pin "3") (pinfunction "P_3") (pintype "passive"))
    )
    (net (code "160") (name "unconnected-(UP-S1-Pad2)") (class "Default")
      (node (ref "UP") (pin "2") (pinfunction "S1_2") (pintype "passive"))
    )
    (net (code "161") (name "unconnected-(Y-S1-Pad2)") (class "Default")
      (node (ref "Y") (pin "2") (pinfunction "S1_2") (pintype "passive"))
    )
  )
)
